# 3__schdoc.net
KiCad netlist of a schematic drawn in Altium Designer
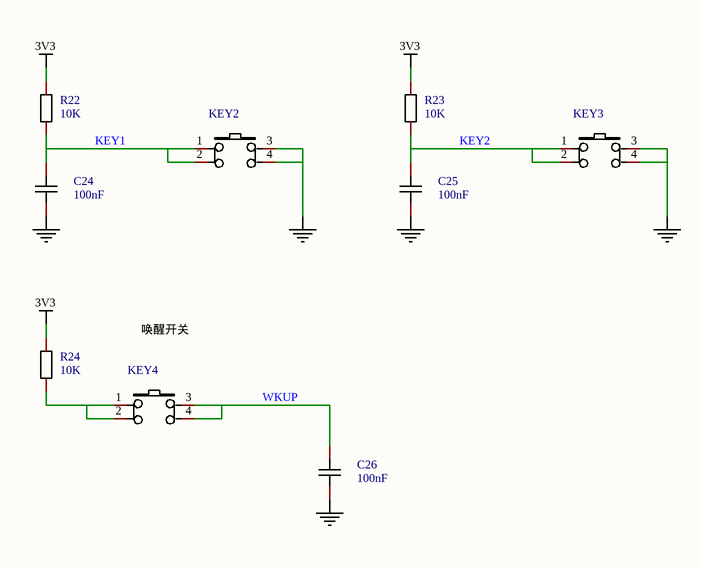
[diagram p0: 3_外设.schdoc.schdoc]

(export (version "E")
  (design (tool "Eeschema 10.0.6"))
  (components
    (comp (ref "C24")
      (value "100nF")
      (fields (field (name "NAME") "100nF"))
      (libsource (lib "altium-import") (part "root_1_CAP_0603_"))
    )
    (comp (ref "C25")
      (value "100nF")
      (fields (field (name "NAME") "100nF"))
      (libsource (lib "altium-import") (part "root_1_CAP_0603_"))
    )
    (comp (ref "C26")
      (value "100nF")
      (fields (field (name "NAME") "100nF"))
      (libsource (lib "altium-import") (part "root_1_CAP_0603_"))
    )
    (comp (ref "KEY2")
      (value "6x6x6塑料头")
      (description "开关长度:6mm;开关宽度:6mm;开关高度:6mm;机械寿命:-;")
      (fields (field (name "MANUFACTURER") "国产"))
      (libsource (lib "altium-import") (part "root_0_6x6x6塑料头_"))
    )
    (comp (ref "KEY3")
      (value "6x6x6塑料头")
      (description "开关长度:6mm;开关宽度:6mm;开关高度:6mm;机械寿命:-;")
      (fields (field (name "MANUFACTURER") "国产"))
      (libsource (lib "altium-import") (part "root_0_6x6x6塑料头_"))
    )
    (comp (ref "KEY4")
      (value "6x6x6塑料头")
      (description "开关长度:6mm;开关宽度:6mm;开关高度:6mm;机械寿命:-;")
      (fields (field (name "MANUFACTURER") "国产"))
      (libsource (lib "altium-import") (part "root_0_6x6x6塑料头_"))
    )
    (comp (ref "R22")
      (value "10K")
      (fields (field (name "NAME") "10K"))
      (libsource (lib "altium-import") (part "root_1_Res_0603_"))
    )
    (comp (ref "R23")
      (value "10K")
      (fields (field (name "NAME") "10K"))
      (libsource (lib "altium-import") (part "root_1_Res_0603_"))
    )
    (comp (ref "R24")
      (value "10K")
      (fields (field (name "NAME") "10K"))
      (libsource (lib "altium-import") (part "root_1_Res_0603_"))
    )
  )
  (nets
    (net (code "1") (name "/KEY1") (class "Default")
      (node (ref "C24") (pin "2") (pinfunction "2_2") (pintype "passive"))
      (node (ref "KEY2") (pin "1") (pinfunction "1_1") (pintype "passive"))
      (node (ref "KEY2") (pin "2") (pinfunction "2_2") (pintype "passive"))
      (node (ref "R22") (pin "1") (pinfunction "1_1") (pintype "passive"))
    )
    (net (code "2") (name "/KEY2") (class "Default")
      (node (ref "C25") (pin "2") (pinfunction "2_2") (pintype "passive"))
      (node (ref "KEY3") (pin "1") (pinfunction "1_1") (pintype "passive"))
      (node (ref "KEY3") (pin "2") (pinfunction "2_2") (pintype "passive"))
      (node (ref "R23") (pin "1") (pinfunction "1_1") (pintype "passive"))
    )
    (net (code "3") (name "/WKUP") (class "Default")
      (node (ref "C26") (pin "2") (pinfunction "2_2") (pintype "passive"))
      (node (ref "KEY4") (pin "3") (pinfunction "3_3") (pintype "passive"))
      (node (ref "KEY4") (pin "4") (pinfunction "4_4") (pintype "passive"))
    )
    (net (code "4") (name "3V3") (class "Default")
      (node (ref "R22") (pin "2") (pinfunction "2_2") (pintype "passive"))
      (node (ref "R23") (pin "2") (pinfunction "2_2") (pintype "passive"))
      (node (ref "R24") (pin "2") (pinfunction "2_2") (pintype "passive"))
    )
    (net (code "5") (name "<NO NET>") (class "Default")
      (node (ref "C24") (pin "1") (pinfunction "1_1") (pintype "passive"))
      (node (ref "C25") (pin "1") (pinfunction "1_1") (pintype "passive"))
      (node (ref "C26") (pin "1") (pinfunction "1_1") (pintype "passive"))
      (node (ref "KEY2") (pin "3") (pinfunction "3_3") (pintype "passive"))
      (node (ref "KEY2") (pin "4") (pinfunction "4_4") (pintype "passive"))
      (node (ref "KEY3") (pin "3") (pinfunction "3_3") (pintype "passive"))
      (node (ref "KEY3") (pin "4") (pinfunction "4_4") (pintype "passive"))
    )
    (net (code "6") (name "Net-(KEY4-Pad1)") (class "Default")
      (node (ref "KEY4") (pin "1") (pinfunction "1_1") (pintype "passive"))
      (node (ref "KEY4") (pin "2") (pinfunction "2_2") (pintype "passive"))
      (node (ref "R24") (pin "1") (pinfunction "1_1") (pintype "passive"))
    )
  )
)
